# SWD_OVER_USB_C.net
KiCad netlist of a schematic drawn in Altium Designer
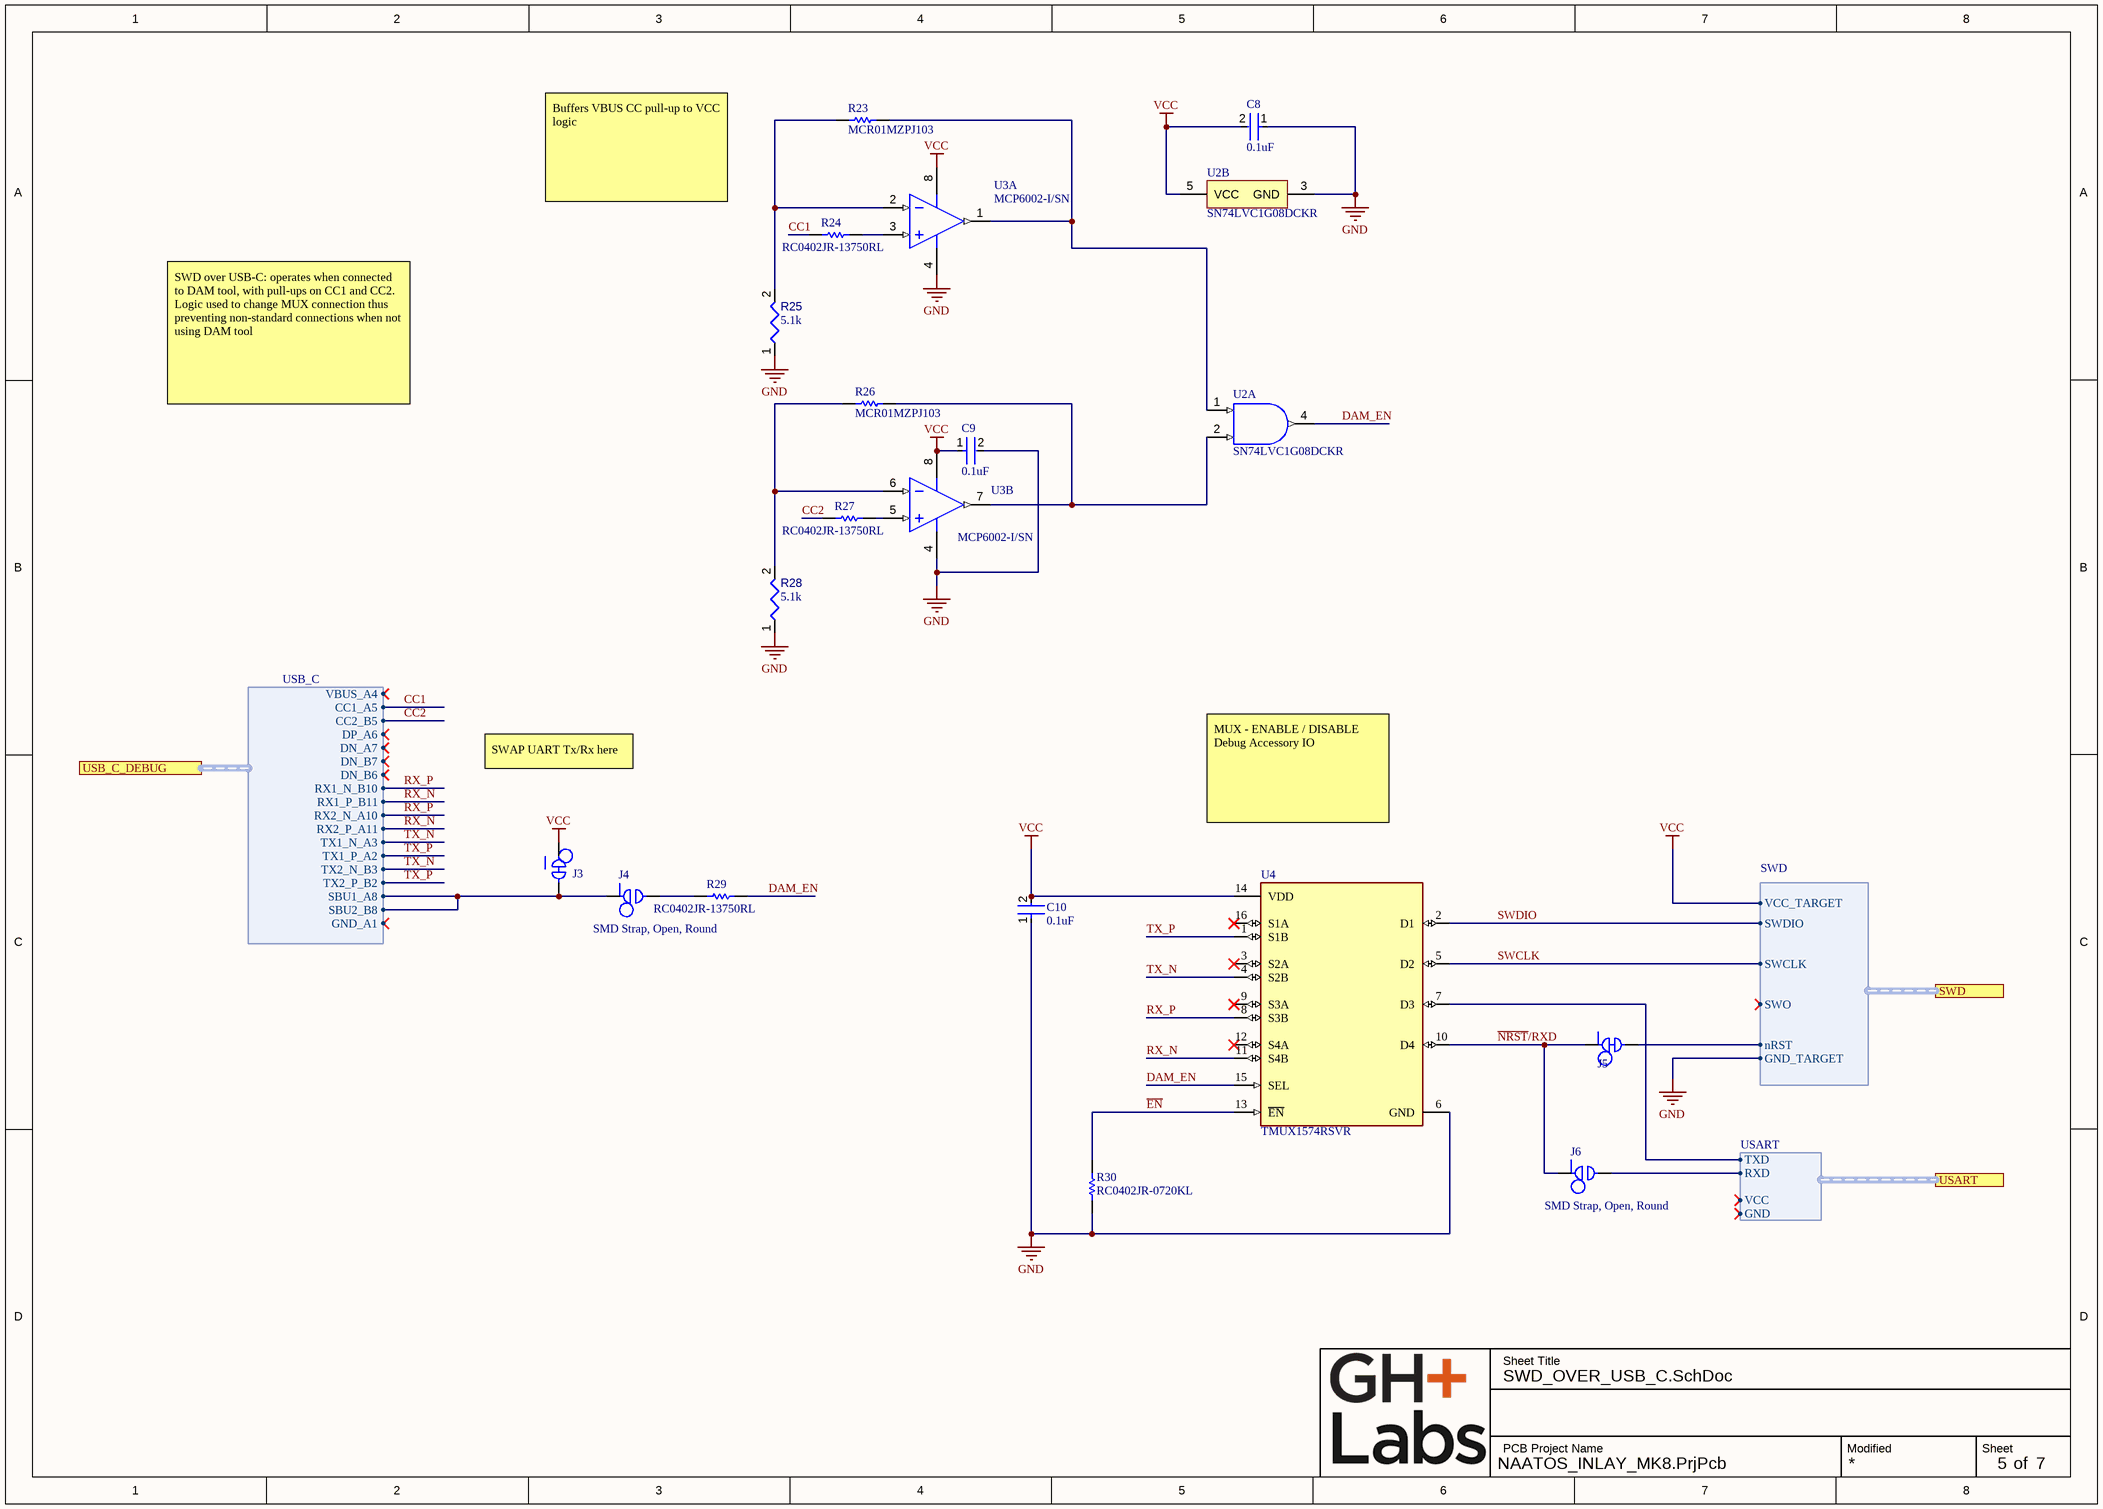
[diagram p0: SWD_OVER_USB_C.SchDoc]

(export (version "E")
  (design (tool "Eeschema 10.0.6"))
  (components
    (comp (ref "C8")
      (value "0.1uF")
      (footprint "FP-CL17-IPC_C")
      (description "Cap Ceramic 100nF 10V X7R ±10% SMD 0402 +125°C Paper T/R")
      (fields (field (name "TOLERANCE") "10%"))
      (libsource (lib "Altium Content Vault") (part "b4654b650e69147ec39a6b967a45e02"))
    )
    (comp (ref "C9")
      (value "0.1uF")
      (footprint "FP-CL17-IPC_C")
      (description "Cap Ceramic 100nF 10V X7R ±10% SMD 0402 +125°C Paper T/R")
      (fields (field (name "TOLERANCE") "10%"))
      (libsource (lib "Altium Content Vault") (part "b4654b650e69147ec39a6b967a45e02"))
    )
    (comp (ref "C10")
      (value "0.1uF")
      (footprint "FP-CL17-IPC_C")
      (description "Cap Ceramic 100nF 10V X7R ±10% SMD 0402 +125°C Paper T/R")
      (fields (field (name "TOLERANCE") "10%"))
      (libsource (lib "Altium Content Vault") (part "b4654b650e69147ec39a6b967a45e02"))
    )
    (comp (ref "J3")
      (value "SMD Strap, 0603, Closed")
      (footprint "JMP-0603-STRAP-CLOSED")
      (libsource (lib "Global Health Labs - Old") (part "SMD-STRAP_CLOSED"))
    )
    (comp (ref "J4")
      (value "SMD Strap, Open, Round")
      (footprint "Open Link, Atmel Design")
      (libsource (lib "Global Health Labs - Old") (part "SMD-STRAP_OPEN"))
    )
    (comp (ref "J5")
      (value "SMD Strap, 0603, Closed")
      (footprint "JMP-0603-STRAP-CLOSED")
      (libsource (lib "Global Health Labs - Old") (part "SMD-STRAP_CLOSED"))
    )
    (comp (ref "J6")
      (value "SMD Strap, Open, Round")
      (footprint "Open Link, Atmel Design")
      (libsource (lib "Global Health Labs - Old") (part "SMD-STRAP_OPEN"))
    )
    (comp (ref "R23")
      (value "MCR01MZPJ103")
      (footprint "RESC1005X40X23LL05T08")
      (description "Chip Resistor, 10 KOhm, +/- 5%, 63 mW, -55 to 155 degC, 0402 (1005 Metric), RoHS, Tape and Reel")
      (fields (field (name "MANUFACTURER") "Rohm"))
      (libsource (lib "Altium Content Vault") (part "RES-2"))
    )
    (comp (ref "R24")
      (value "RC0402JR-13750RL")
      (footprint "RESC1005X40X25LL05T10")
      (fields (field (name "MANUFACTURER") "Yageo"))
      (libsource (lib "Altium Content Vault") (part "RES"))
    )
    (comp (ref "R25")
      (value "5.1k")
      (footprint "RESC0402(1005)_L")
      (description "Chip Resistor, 5.1 kOhms, +/-1 %, 63 mW, -55 to 155 degC, 0402")
      (fields (field (name "POWER") "63mW") (field (name "TOLERANCE") "1%"))
      (libsource (lib "Global Health Labs, Inc") (part "RES-2"))
    )
    (comp (ref "R26")
      (value "MCR01MZPJ103")
      (footprint "RESC1005X40X23LL05T08")
      (description "Chip Resistor, 10 KOhm, +/- 5%, 63 mW, -55 to 155 degC, 0402 (1005 Metric), RoHS, Tape and Reel")
      (fields (field (name "MANUFACTURER") "Rohm"))
      (libsource (lib "Altium Content Vault") (part "RES-2"))
    )
    (comp (ref "R27")
      (value "RC0402JR-13750RL")
      (footprint "RESC1005X40X25LL05T10")
      (fields (field (name "MANUFACTURER") "Yageo"))
      (libsource (lib "Altium Content Vault") (part "RES"))
    )
    (comp (ref "R28")
      (value "5.1k")
      (footprint "RESC0402(1005)_L")
      (description "Chip Resistor, 5.1 kOhms, +/-1 %, 63 mW, -55 to 155 degC, 0402")
      (fields (field (name "POWER") "63mW") (field (name "TOLERANCE") "1%"))
      (libsource (lib "Global Health Labs, Inc") (part "RES-2"))
    )
    (comp (ref "R29")
      (value "RC0402JR-13750RL")
      (footprint "RESC1005X40X25LL05T10")
      (fields (field (name "MANUFACTURER") "Yageo"))
      (libsource (lib "Altium Content Vault") (part "RES"))
    )
    (comp (ref "R30")
      (value "RC0402JR-0720KL")
      (footprint "RESC1005X40X25NL05T10")
      (fields (field (name "MANUFACTURER") "Yageo / Phycomp"))
      (libsource (lib "Altium Content Vault") (part "RES"))
    )
    (comp (ref "U2")
      (value "SN74LVC1G08DCKR")
      (footprint "DCK0005A_M")
      (description "Single 2-Input Positive-AND Gate, DCK0005A, LARGE T&R")
      (fields
        (field (name "GENERIC PART NUMBER") "SN74LVC1G08")
        (field (name "MANUFACTURER") "Texas Instruments")
      )
      (libsource (lib "Altium Content Vault") (part "TI-SN74XXX1X08-5"))
    )
    (comp (ref "U3")
      (value "MCP6002-I/SN")
      (footprint "SOIC-SN8_M")
      (description "None")
      (libsource (lib "Altium Content Vault") (part "AMP-OPA-MCP6002-IL8"))
    )
    (comp (ref "U4")
      (value "TMUX1574RSVR")
      (footprint "FP-RSV0016A-MFG")
      (description "IC SWITCH SPDT QUAD 16UQFN")
      (libsource (lib "Altium Content Vault") (part "6ae91f3a9e3ea7621a49082f656dcdc"))
    )
  )
  (nets
    (net (code "4") (name "/CC1") (class "Default")
      (node (ref "R24") (pin "1") (pinfunction "1_1") (pintype "passive"))
    )
    (net (code "5") (name "/CC2") (class "Default")
      (node (ref "R27") (pin "1") (pinfunction "1_1") (pintype "passive"))
    )
    (net (code "6") (name "/DAM_EN") (class "Default")
      (node (ref "R29") (pin "2") (pinfunction "2_2") (pintype "passive"))
      (node (ref "U2") (pin "4") (pinfunction "Y_4") (pintype "output"))
      (node (ref "U4") (pin "15") (pinfunction "SEL_15") (pintype "input"))
    )
    (net (code "7") (name "/RXD") (class "Default")
      (node (ref "J6") (pin "2") (pinfunction "2_2") (pintype "passive"))
    )
    (net (code "8") (name "/RX_N") (class "Default")
      (node (ref "U4") (pin "11") (pinfunction "S4B_11") (pintype "bidirectional"))
    )
    (net (code "9") (name "/RX_P") (class "Default")
      (node (ref "U4") (pin "8") (pinfunction "S3B_8") (pintype "bidirectional"))
    )
    (net (code "10") (name "/SBU1_A8") (class "Default")
      (node (ref "J3") (pin "2") (pinfunction "2_2") (pintype "passive"))
      (node (ref "J4") (pin "1") (pinfunction "1_1") (pintype "passive"))
    )
    (net (code "11") (name "/SWCLK") (class "Default")
      (node (ref "U4") (pin "5") (pinfunction "D2_5") (pintype "bidirectional"))
    )
    (net (code "12") (name "/SWDIO") (class "Default")
      (node (ref "U4") (pin "2") (pinfunction "D1_2") (pintype "bidirectional"))
    )
    (net (code "13") (name "/TXD") (class "Default")
      (node (ref "U4") (pin "7") (pinfunction "D3_7") (pintype "bidirectional"))
    )
    (net (code "14") (name "/TX_N") (class "Default")
      (node (ref "U4") (pin "4") (pinfunction "S2B_4") (pintype "bidirectional"))
    )
    (net (code "15") (name "/TX_P") (class "Default")
      (node (ref "U4") (pin "1") (pinfunction "S1B_1") (pintype "bidirectional"))
    )
    (net (code "16") (name "/nRST") (class "Default")
      (node (ref "J5") (pin "2") (pinfunction "2_2") (pintype "passive"))
    )
    (net (code "20") (name "/~{EN}") (class "Default")
      (node (ref "R30") (pin "2") (pinfunction "2_2") (pintype "passive"))
      (node (ref "U4") (pin "13") (pinfunction "~{EN}_13") (pintype "input"))
    )
    (net (code "21") (name "/~{NRST}{slash}RXD") (class "Default")
      (node (ref "J5") (pin "1") (pinfunction "1_1") (pintype "passive"))
      (node (ref "J6") (pin "1") (pinfunction "1_1") (pintype "passive"))
      (node (ref "U4") (pin "10") (pinfunction "D4_10") (pintype "bidirectional"))
    )
    (net (code "22") (name "GND") (class "Default")
      (node (ref "C10") (pin "1") (pinfunction "1_1") (pintype "passive"))
      (node (ref "C8") (pin "1") (pinfunction "1_1") (pintype "passive"))
      (node (ref "C9") (pin "2") (pinfunction "2_2") (pintype "passive"))
      (node (ref "R25") (pin "1") (pinfunction "1_1") (pintype "passive"))
      (node (ref "R28") (pin "1") (pinfunction "1_1") (pintype "passive"))
      (node (ref "R30") (pin "1") (pinfunction "1_1") (pintype "passive"))
      (node (ref "U2") (pin "3") (pinfunction "GND_3") (pintype "power_in"))
      (node (ref "U3") (pin "4") (pinfunction "VSS_4") (pintype "power_in"))
      (node (ref "U4") (pin "6") (pinfunction "GND_6") (pintype "power_in"))
    )
    (net (code "23") (name "Net-(J4-Pad2)") (class "Default")
      (node (ref "J4") (pin "2") (pinfunction "2_2") (pintype "passive"))
      (node (ref "R29") (pin "1") (pinfunction "1_1") (pintype "passive"))
    )
    (net (code "24") (name "Net-(U2A-A)") (class "Default")
      (node (ref "R23") (pin "2") (pinfunction "2_2") (pintype "passive"))
      (node (ref "U2") (pin "1") (pinfunction "A_1") (pintype "input"))
      (node (ref "U3") (pin "1") (pinfunction "VOUTA_1") (pintype "output"))
    )
    (net (code "25") (name "Net-(U2A-B)") (class "Default")
      (node (ref "R26") (pin "2") (pinfunction "2_2") (pintype "passive"))
      (node (ref "U2") (pin "2") (pinfunction "B_2") (pintype "input"))
      (node (ref "U3") (pin "7") (pinfunction "VOUTB_7") (pintype "output"))
    )
    (net (code "26") (name "Net-(U3A-VINA+)") (class "Default")
      (node (ref "R24") (pin "2") (pinfunction "2_2") (pintype "passive"))
      (node (ref "U3") (pin "3") (pinfunction "VINA+_3") (pintype "input"))
    )
    (net (code "27") (name "Net-(U3A-VINA-)") (class "Default")
      (node (ref "R23") (pin "1") (pinfunction "1_1") (pintype "passive"))
      (node (ref "R25") (pin "2") (pinfunction "2_2") (pintype "passive"))
      (node (ref "U3") (pin "2") (pinfunction "VINA-_2") (pintype "input"))
    )
    (net (code "28") (name "Net-(U3B-VINB+)") (class "Default")
      (node (ref "R27") (pin "2") (pinfunction "2_2") (pintype "passive"))
      (node (ref "U3") (pin "5") (pinfunction "VINB+_5") (pintype "input"))
    )
    (net (code "29") (name "Net-(U3B-VINB-)") (class "Default")
      (node (ref "R26") (pin "1") (pinfunction "1_1") (pintype "passive"))
      (node (ref "R28") (pin "2") (pinfunction "2_2") (pintype "passive"))
      (node (ref "U3") (pin "6") (pinfunction "VINB-_6") (pintype "input"))
    )
    (net (code "30") (name "VCC") (class "Default")
      (node (ref "C10") (pin "2") (pinfunction "2_2") (pintype "passive"))
      (node (ref "C8") (pin "2") (pinfunction "2_2") (pintype "passive"))
      (node (ref "C9") (pin "1") (pinfunction "1_1") (pintype "passive"))
      (node (ref "J3") (pin "1") (pinfunction "1_1") (pintype "passive"))
      (node (ref "U2") (pin "5") (pinfunction "VCC_5") (pintype "power_in"))
      (node (ref "U3") (pin "8") (pinfunction "VDD_8") (pintype "power_in"))
      (node (ref "U4") (pin "14") (pinfunction "VDD_14") (pintype "power_in"))
    )
    (net (code "31") (name "unconnected-(U4-S1A-Pad16)") (class "Default")
      (node (ref "U4") (pin "16") (pinfunction "S1A_16") (pintype "bidirectional+no_connect"))
    )
    (net (code "32") (name "unconnected-(U4-S2A-Pad3)") (class "Default")
      (node (ref "U4") (pin "3") (pinfunction "S2A_3") (pintype "bidirectional+no_connect"))
    )
    (net (code "33") (name "unconnected-(U4-S3A-Pad9)") (class "Default")
      (node (ref "U4") (pin "9") (pinfunction "S3A_9") (pintype "bidirectional+no_connect"))
    )
    (net (code "34") (name "unconnected-(U4-S4A-Pad12)") (class "Default")
      (node (ref "U4") (pin "12") (pinfunction "S4A_12") (pintype "bidirectional+no_connect"))
    )
  )
)
